# main.net
KiCad netlist of a schematic drawn in EAGLE
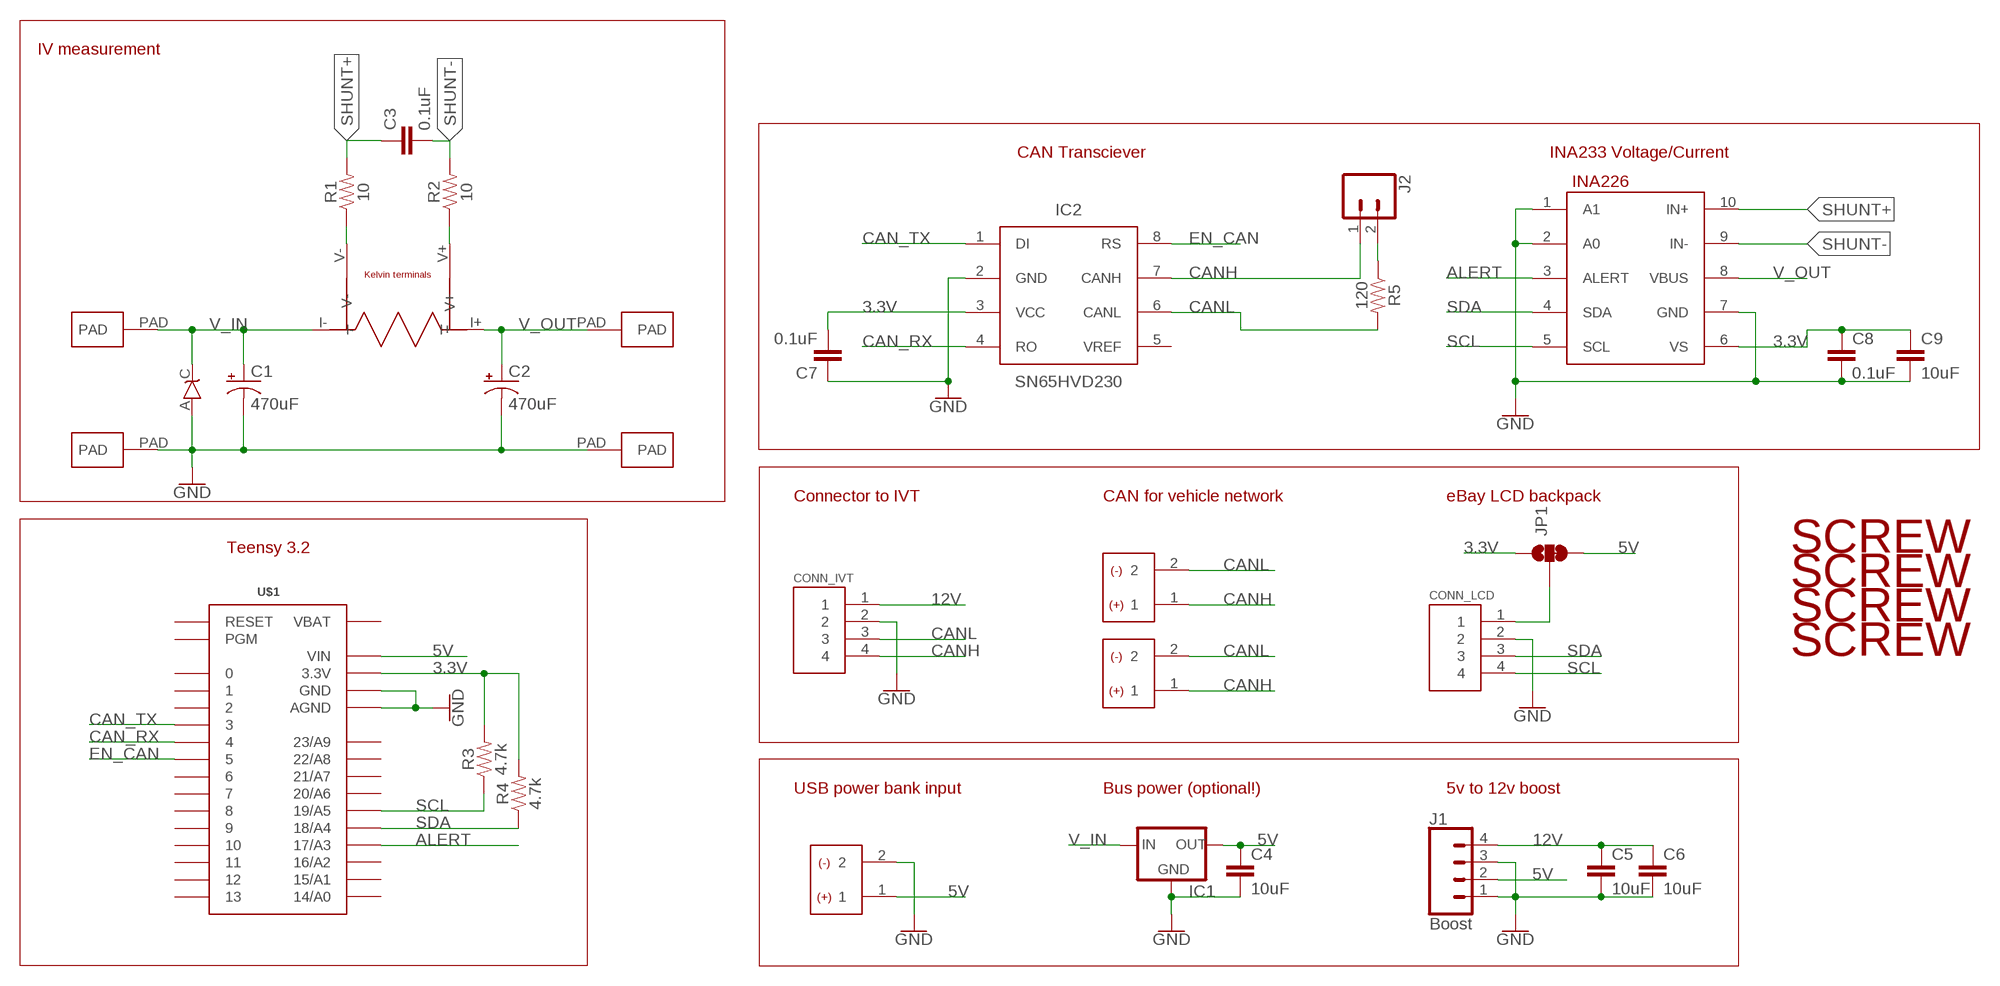
[diagram p0: schematic, sheet 1]

(export (version "E")
  (design (tool "Eeschema 10.0.6"))
  (components
    (comp (ref "C1")
      (value "470uF")
      (footprint "eagle-import:CPOL-RADIAL-5MM-10MM")
      (libsource (lib "eagle-import") (part "1000UF-RADIAL-5MM-25V-20%"))
    )
    (comp (ref "C2")
      (value "470uF")
      (footprint "eagle-import:CPOL-RADIAL-5MM-10MM")
      (libsource (lib "eagle-import") (part "1000UF-RADIAL-5MM-25V-20%"))
    )
    (comp (ref "C3")
      (value "0.1uF")
      (footprint "eagle-import:0603")
      (libsource (lib "eagle-import") (part "0.1UF-0603-25V-5%"))
    )
    (comp (ref "C4")
      (value "10uF")
      (footprint "eagle-import:1210")
      (libsource (lib "eagle-import") (part "10UF-1210-50V-20%"))
    )
    (comp (ref "C5")
      (value "10uF")
      (footprint "eagle-import:1210")
      (libsource (lib "eagle-import") (part "10UF-1210-50V-20%"))
    )
    (comp (ref "C6")
      (value "10uF")
      (footprint "eagle-import:1210")
      (libsource (lib "eagle-import") (part "10UF-1210-50V-20%"))
    )
    (comp (ref "C7")
      (value "0.1uF")
      (footprint "eagle-import:0603")
      (libsource (lib "eagle-import") (part "0.1UF-0603-25V-5%"))
    )
    (comp (ref "C8")
      (value "0.1uF")
      (footprint "eagle-import:0603")
      (libsource (lib "eagle-import") (part "0.1UF-0603-25V-5%"))
    )
    (comp (ref "C9")
      (value "10uF")
      (footprint "eagle-import:1210")
      (libsource (lib "eagle-import") (part "10UF-1210-50V-20%"))
    )
    (comp (ref "CONN_IVT")
      (value "LCD")
      (footprint "eagle-import:4PINVALULOK")
      (libsource (lib "eagle-import") (part "HEADER4VALULOK"))
    )
    (comp (ref "CONN_LCD")
      (value "LCD")
      (footprint "eagle-import:4PINVALULOK")
      (libsource (lib "eagle-import") (part "HEADER4VALULOK"))
    )
    (comp (ref "IC1")
      (value "V_REG_78XX")
      (footprint "eagle-import:V78W_BACKWARDS")
      (libsource (lib "eagle-import") (part "V_REG_78XX"))
    )
    (comp (ref "IC2")
      (value "SN65HVD230")
      (footprint "eagle-import:SOIC127P650X175-8")
      (libsource (lib "eagle-import") (part "SN65HVD230SOIC-8"))
    )
    (comp (ref "J1")
      (value "Boost")
      (footprint "eagle-import:1X04_LONGPADS")
      (libsource (lib "eagle-import") (part "CONN_04LONGPADS"))
    )
    (comp (ref "J2")
      (value "CONN_02")
      (footprint "eagle-import:1X02")
      (libsource (lib "eagle-import") (part "CONN_02"))
    )
    (comp (ref "JP1")
      (value "JUMPER-SMT_3_1-NC_TRACE_SILK")
      (footprint "eagle-import:SMT-JUMPER_3_1-NC_TRACE_SILK")
      (libsource (lib "eagle-import") (part "JUMPER-SMT_3_1-NC_TRACE_SILK"))
    )
    (comp (ref "R1")
      (value "10")
      (footprint "eagle-import:0603")
      (libsource (lib "eagle-import") (part "RESISTOR0603"))
    )
    (comp (ref "R2")
      (value "10")
      (footprint "eagle-import:0603")
      (libsource (lib "eagle-import") (part "RESISTOR0603"))
    )
    (comp (ref "R3")
      (value "4.7k")
      (footprint "eagle-import:0603")
      (libsource (lib "eagle-import") (part "RESISTOR0603"))
    )
    (comp (ref "R4")
      (value "4.7k")
      (footprint "eagle-import:0603")
      (libsource (lib "eagle-import") (part "RESISTOR0603"))
    )
    (comp (ref "R5")
      (value "120")
      (footprint "eagle-import:0603")
      (libsource (lib "eagle-import") (part "RESISTOR0603"))
    )
    (comp (ref "U$1")
      (value "TEENSY_3.0_BASIC")
      (footprint "eagle-import:TEENSY_3.0_BASIC")
      (libsource (lib "eagle-import") (part "TEENSY_3.0_BASIC"))
    )
    (comp (ref "U$2")
      (value "5mOhm")
      (footprint "eagle-import:2512_KELVIN")
      (libsource (lib "eagle-import") (part "SHUNT_KELVIN"))
    )
    (comp (ref "U$3")
      (value "PAD")
      (footprint "eagle-import:PAD")
      (libsource (lib "eagle-import") (part "PAD"))
    )
    (comp (ref "U$4")
      (value "PAD")
      (footprint "eagle-import:PAD")
      (libsource (lib "eagle-import") (part "PAD"))
    )
    (comp (ref "U$5")
      (value "INA226")
      (footprint "eagle-import:PSOP-10")
      (libsource (lib "eagle-import") (part "INA226"))
    )
    (comp (ref "U$6")
      (value "TVS_UNIDO-214AC")
      (footprint "eagle-import:DO-214AC")
      (libsource (lib "eagle-import") (part "TVS_UNIDO-214AC"))
    )
    (comp (ref "U$7")
      (value "PAD")
      (footprint "eagle-import:PAD")
      (libsource (lib "eagle-import") (part "PAD"))
    )
    (comp (ref "U$8")
      (value "PAD")
      (footprint "eagle-import:PAD")
      (libsource (lib "eagle-import") (part "PAD"))
    )
    (comp (ref "U$9")
      (value "HEADER2")
      (footprint "eagle-import:2PINVALULOK")
      (libsource (lib "eagle-import") (part "HEADER2"))
    )
    (comp (ref "U$10")
      (value "HEADER2")
      (footprint "eagle-import:2PINVALULOK")
      (libsource (lib "eagle-import") (part "HEADER2"))
    )
    (comp (ref "U$11")
      (value "SCREW")
      (footprint "eagle-import:M3HOLE")
      (libsource (lib "eagle-import") (part "SCREW"))
    )
    (comp (ref "U$12")
      (value "SCREW")
      (footprint "eagle-import:M3HOLE")
      (libsource (lib "eagle-import") (part "SCREW"))
    )
    (comp (ref "U$13")
      (value "SCREW")
      (footprint "eagle-import:M3HOLE")
      (libsource (lib "eagle-import") (part "SCREW"))
    )
    (comp (ref "U$14")
      (value "SCREW")
      (footprint "eagle-import:M3HOLE")
      (libsource (lib "eagle-import") (part "SCREW"))
    )
    (comp (ref "USB_PWR")
      (value "USB_PWR")
      (footprint "eagle-import:2PINVALULOK")
      (libsource (lib "eagle-import") (part "HEADER2"))
    )
  )
  (nets
    (net (code "1") (name "/3.3V") (class "Default")
      (node (ref "C7") (pin "2") (pinfunction "2_2") (pintype "passive"))
      (node (ref "C8") (pin "1") (pinfunction "1_1") (pintype "passive"))
      (node (ref "C9") (pin "1") (pinfunction "1_1") (pintype "passive"))
      (node (ref "IC2") (pin "3") (pinfunction "VCC_3") (pintype "power_in"))
      (node (ref "JP1") (pin "1") (pinfunction "1_1") (pintype "passive"))
      (node (ref "R3") (pin "2") (pinfunction "2_2") (pintype "passive"))
      (node (ref "R4") (pin "2") (pinfunction "2_2") (pintype "passive"))
      (node (ref "U$1") (pin "3.3V") (pinfunction "3.3V_3.3V") (pintype "power_in"))
      (node (ref "U$1") (pin "3.3V1") (pinfunction "3.3V_3.3V1") (pintype "power_in"))
      (node (ref "U$5") (pin "6") (pinfunction "VS_6") (pintype "bidirectional"))
    )
    (net (code "2") (name "/5V") (class "Default")
      (node (ref "C4") (pin "1") (pinfunction "1_1") (pintype "passive"))
      (node (ref "IC1") (pin "OUT") (pinfunction "OUT_OUT") (pintype "output"))
      (node (ref "J1") (pin "2") (pinfunction "2_2") (pintype "passive"))
      (node (ref "JP1") (pin "3") (pinfunction "3_3") (pintype "passive"))
      (node (ref "U$1") (pin "VIN") (pinfunction "VIN_VIN") (pintype "power_in"))
      (node (ref "USB_PWR") (pin "1") (pinfunction "1_1") (pintype "bidirectional"))
    )
    (net (code "3") (name "/12V") (class "Default")
      (node (ref "C5") (pin "1") (pinfunction "1_1") (pintype "passive"))
      (node (ref "C6") (pin "1") (pinfunction "1_1") (pintype "passive"))
      (node (ref "CONN_IVT") (pin "1") (pinfunction "1_1") (pintype "bidirectional"))
      (node (ref "J1") (pin "4") (pinfunction "4_4") (pintype "passive"))
    )
    (net (code "4") (name "/ALERT") (class "Default")
      (node (ref "U$1") (pin "17/A3") (pinfunction "17/A3_17/A3") (pintype "bidirectional"))
      (node (ref "U$5") (pin "3") (pinfunction "ALERT_3") (pintype "bidirectional"))
    )
    (net (code "5") (name "/CANH") (class "Default")
      (node (ref "CONN_IVT") (pin "4") (pinfunction "4_4") (pintype "bidirectional"))
      (node (ref "IC2") (pin "7") (pinfunction "CANH_7") (pintype "bidirectional"))
      (node (ref "J2") (pin "1") (pinfunction "1_1") (pintype "passive"))
      (node (ref "U$10") (pin "1") (pinfunction "1_1") (pintype "bidirectional"))
      (node (ref "U$9") (pin "1") (pinfunction "1_1") (pintype "bidirectional"))
    )
    (net (code "6") (name "/CANL") (class "Default")
      (node (ref "CONN_IVT") (pin "3") (pinfunction "3_3") (pintype "bidirectional"))
      (node (ref "IC2") (pin "6") (pinfunction "CANL_6") (pintype "bidirectional"))
      (node (ref "R5") (pin "2") (pinfunction "2_2") (pintype "passive"))
      (node (ref "U$10") (pin "2") (pinfunction "2_2") (pintype "bidirectional"))
      (node (ref "U$9") (pin "2") (pinfunction "2_2") (pintype "bidirectional"))
    )
    (net (code "7") (name "/CAN_RX") (class "Default")
      (node (ref "IC2") (pin "4") (pinfunction "RO_4") (pintype "output"))
      (node (ref "U$1") (pin "4") (pinfunction "4_4") (pintype "bidirectional"))
    )
    (net (code "8") (name "/CAN_TX") (class "Default")
      (node (ref "IC2") (pin "1") (pinfunction "DI_1") (pintype "input"))
      (node (ref "U$1") (pin "3") (pinfunction "3_3") (pintype "bidirectional"))
    )
    (net (code "9") (name "/EN_CAN") (class "Default")
      (node (ref "IC2") (pin "8") (pinfunction "RS_8") (pintype "input"))
      (node (ref "U$1") (pin "5") (pinfunction "5_5") (pintype "bidirectional"))
    )
    (net (code "10") (name "/SCL") (class "Default")
      (node (ref "CONN_LCD") (pin "4") (pinfunction "4_4") (pintype "bidirectional"))
      (node (ref "R3") (pin "1") (pinfunction "1_1") (pintype "passive"))
      (node (ref "U$1") (pin "19/A5") (pinfunction "19/A5_19/A5") (pintype "bidirectional"))
      (node (ref "U$5") (pin "5") (pinfunction "SCL_5") (pintype "bidirectional"))
    )
    (net (code "11") (name "/SDA") (class "Default")
      (node (ref "CONN_LCD") (pin "3") (pinfunction "3_3") (pintype "bidirectional"))
      (node (ref "R4") (pin "1") (pinfunction "1_1") (pintype "passive"))
      (node (ref "U$1") (pin "18/A4") (pinfunction "18/A4_18/A4") (pintype "bidirectional"))
      (node (ref "U$5") (pin "4") (pinfunction "SDA_4") (pintype "bidirectional"))
    )
    (net (code "12") (name "/VBAT") (class "Default")
      (node (ref "U$1") (pin "VBAT") (pinfunction "VBAT_VBAT") (pintype "power_in"))
    )
    (net (code "13") (name "/V_IN") (class "Default")
      (node (ref "C1") (pin "+") (pinfunction "+_+") (pintype "passive"))
      (node (ref "IC1") (pin "IN") (pinfunction "IN_IN") (pintype "input"))
      (node (ref "U$2") (pin "I-") (pinfunction "I-_I-") (pintype "bidirectional"))
      (node (ref "U$3") (pin "PAD") (pinfunction "PAD_PAD") (pintype "bidirectional"))
      (node (ref "U$6") (pin "C") (pinfunction "C_C") (pintype "bidirectional"))
    )
    (net (code "14") (name "/V_OUT") (class "Default")
      (node (ref "C2") (pin "+") (pinfunction "+_+") (pintype "passive"))
      (node (ref "U$2") (pin "I+") (pinfunction "I+_I+") (pintype "bidirectional"))
      (node (ref "U$5") (pin "8") (pinfunction "VBUS_8") (pintype "bidirectional"))
      (node (ref "U$7") (pin "PAD") (pinfunction "PAD_PAD") (pintype "bidirectional"))
    )
    (net (code "15") (name "GND") (class "Default")
      (node (ref "C1") (pin "-") (pinfunction "-_-") (pintype "passive"))
      (node (ref "C2") (pin "-") (pinfunction "-_-") (pintype "passive"))
      (node (ref "C4") (pin "2") (pinfunction "2_2") (pintype "passive"))
      (node (ref "C5") (pin "2") (pinfunction "2_2") (pintype "passive"))
      (node (ref "C6") (pin "2") (pinfunction "2_2") (pintype "passive"))
      (node (ref "C7") (pin "1") (pinfunction "1_1") (pintype "passive"))
      (node (ref "C8") (pin "2") (pinfunction "2_2") (pintype "passive"))
      (node (ref "C9") (pin "2") (pinfunction "2_2") (pintype "passive"))
      (node (ref "CONN_IVT") (pin "2") (pinfunction "2_2") (pintype "bidirectional"))
      (node (ref "CONN_LCD") (pin "2") (pinfunction "2_2") (pintype "bidirectional"))
      (node (ref "IC1") (pin "GND") (pinfunction "GND_GND") (pintype "input"))
      (node (ref "IC2") (pin "2") (pinfunction "GND_2") (pintype "power_in"))
      (node (ref "J1") (pin "1") (pinfunction "1_1") (pintype "passive"))
      (node (ref "J1") (pin "3") (pinfunction "3_3") (pintype "passive"))
      (node (ref "U$1") (pin "AGND") (pinfunction "AGND_AGND") (pintype "power_in"))
      (node (ref "U$1") (pin "GND") (pinfunction "GND_GND") (pintype "power_in"))
      (node (ref "U$1") (pin "GND1") (pinfunction "GND_GND1") (pintype "power_in"))
      (node (ref "U$4") (pin "PAD") (pinfunction "PAD_PAD") (pintype "bidirectional"))
      (node (ref "U$5") (pin "1") (pinfunction "A1_1") (pintype "bidirectional"))
      (node (ref "U$5") (pin "2") (pinfunction "A0_2") (pintype "bidirectional"))
      (node (ref "U$5") (pin "7") (pinfunction "GND_7") (pintype "bidirectional"))
      (node (ref "U$6") (pin "A") (pinfunction "A_A") (pintype "bidirectional"))
      (node (ref "U$8") (pin "PAD") (pinfunction "PAD_PAD") (pintype "bidirectional"))
      (node (ref "USB_PWR") (pin "2") (pinfunction "2_2") (pintype "bidirectional"))
    )
    (net (code "16") (name "Net-(CONN_LCD-Pad1)") (class "Default")
      (node (ref "CONN_LCD") (pin "1") (pinfunction "1_1") (pintype "bidirectional"))
      (node (ref "JP1") (pin "2") (pinfunction "2_2") (pintype "passive"))
    )
    (net (code "17") (name "Net-(J2-Pad2)") (class "Default")
      (node (ref "J2") (pin "2") (pinfunction "2_2") (pintype "passive"))
      (node (ref "R5") (pin "1") (pinfunction "1_1") (pintype "passive"))
    )
    (net (code "18") (name "Net-(R1-Pad1)") (class "Default")
      (node (ref "R1") (pin "1") (pinfunction "1_1") (pintype "passive"))
      (node (ref "U$2") (pin "V-") (pinfunction "V-_V-") (pintype "bidirectional"))
    )
    (net (code "19") (name "Net-(R2-Pad1)") (class "Default")
      (node (ref "R2") (pin "1") (pinfunction "1_1") (pintype "passive"))
      (node (ref "U$2") (pin "V+") (pinfunction "V+_V+") (pintype "bidirectional"))
    )
    (net (code "20") (name "SHUNT+") (class "Default")
      (node (ref "C3") (pin "1") (pinfunction "1_1") (pintype "passive"))
      (node (ref "R1") (pin "2") (pinfunction "2_2") (pintype "passive"))
      (node (ref "U$5") (pin "10") (pinfunction "IN+_10") (pintype "bidirectional"))
    )
    (net (code "21") (name "SHUNT-") (class "Default")
      (node (ref "C3") (pin "2") (pinfunction "2_2") (pintype "passive"))
      (node (ref "R2") (pin "2") (pinfunction "2_2") (pintype "passive"))
      (node (ref "U$5") (pin "9") (pinfunction "IN-_9") (pintype "bidirectional"))
    )
    (net (code "22") (name "unconnected-(IC2-VREF-Pad5)") (class "Default")
      (node (ref "IC2") (pin "5") (pinfunction "VREF_5") (pintype "output"))
    )
    (net (code "23") (name "unconnected-(U$1-Pad0)") (class "Default")
      (node (ref "U$1") (pin "0") (pinfunction "0_0") (pintype "bidirectional"))
    )
    (net (code "24") (name "unconnected-(U$1-Pad1)") (class "Default")
      (node (ref "U$1") (pin "1") (pinfunction "1_1") (pintype "bidirectional"))
    )
    (net (code "25") (name "unconnected-(U$1-Pad2)") (class "Default")
      (node (ref "U$1") (pin "2") (pinfunction "2_2") (pintype "bidirectional"))
    )
    (net (code "26") (name "unconnected-(U$1-Pad6)") (class "Default")
      (node (ref "U$1") (pin "6") (pinfunction "6_6") (pintype "bidirectional"))
    )
    (net (code "27") (name "unconnected-(U$1-Pad7)") (class "Default")
      (node (ref "U$1") (pin "7") (pinfunction "7_7") (pintype "bidirectional"))
    )
    (net (code "28") (name "unconnected-(U$1-Pad8)") (class "Default")
      (node (ref "U$1") (pin "8") (pinfunction "8_8") (pintype "bidirectional"))
    )
    (net (code "29") (name "unconnected-(U$1-Pad9)") (class "Default")
      (node (ref "U$1") (pin "9") (pinfunction "9_9") (pintype "bidirectional"))
    )
    (net (code "30") (name "unconnected-(U$1-Pad10)") (class "Default")
      (node (ref "U$1") (pin "10") (pinfunction "10_10") (pintype "bidirectional"))
    )
    (net (code "31") (name "unconnected-(U$1-Pad11)") (class "Default")
      (node (ref "U$1") (pin "11") (pinfunction "11_11") (pintype "bidirectional"))
    )
    (net (code "32") (name "unconnected-(U$1-Pad12)") (class "Default")
      (node (ref "U$1") (pin "12") (pinfunction "12_12") (pintype "bidirectional"))
    )
    (net (code "33") (name "unconnected-(U$1-Pad13)") (class "Default")
      (node (ref "U$1") (pin "13") (pinfunction "13_13") (pintype "bidirectional"))
    )
    (net (code "34") (name "unconnected-(U$1-Pad14{slash}A0)") (class "Default")
      (node (ref "U$1") (pin "14/A0") (pinfunction "14/A0_14/A0") (pintype "bidirectional"))
    )
    (net (code "35") (name "unconnected-(U$1-Pad15{slash}A1)") (class "Default")
      (node (ref "U$1") (pin "15/A1") (pinfunction "15/A1_15/A1") (pintype "bidirectional"))
    )
    (net (code "36") (name "unconnected-(U$1-Pad16{slash}A2)") (class "Default")
      (node (ref "U$1") (pin "16/A2") (pinfunction "16/A2_16/A2") (pintype "bidirectional"))
    )
    (net (code "37") (name "unconnected-(U$1-Pad20{slash}A6)") (class "Default")
      (node (ref "U$1") (pin "20/A6") (pinfunction "20/A6_20/A6") (pintype "bidirectional"))
    )
    (net (code "38") (name "unconnected-(U$1-Pad21{slash}A7)") (class "Default")
      (node (ref "U$1") (pin "21/A7") (pinfunction "21/A7_21/A7") (pintype "bidirectional"))
    )
    (net (code "39") (name "unconnected-(U$1-Pad22{slash}A8)") (class "Default")
      (node (ref "U$1") (pin "22/A8") (pinfunction "22/A8_22/A8") (pintype "bidirectional"))
    )
    (net (code "40") (name "unconnected-(U$1-Pad23{slash}A9)") (class "Default")
      (node (ref "U$1") (pin "23/A9") (pinfunction "23/A9_23/A9") (pintype "bidirectional"))
    )
    (net (code "41") (name "unconnected-(U$1-PadPGM)") (class "Default")
      (node (ref "U$1") (pin "PGM") (pinfunction "PGM_PGM") (pintype "bidirectional"))
    )
    (net (code "42") (name "unconnected-(U$1-PadRESET)") (class "Default")
      (node (ref "U$1") (pin "RESET") (pinfunction "RESET_RESET") (pintype "bidirectional"))
    )
  )
)
